# Half-Bridge.net
KiCad netlist of a schematic drawn in Altium Designer
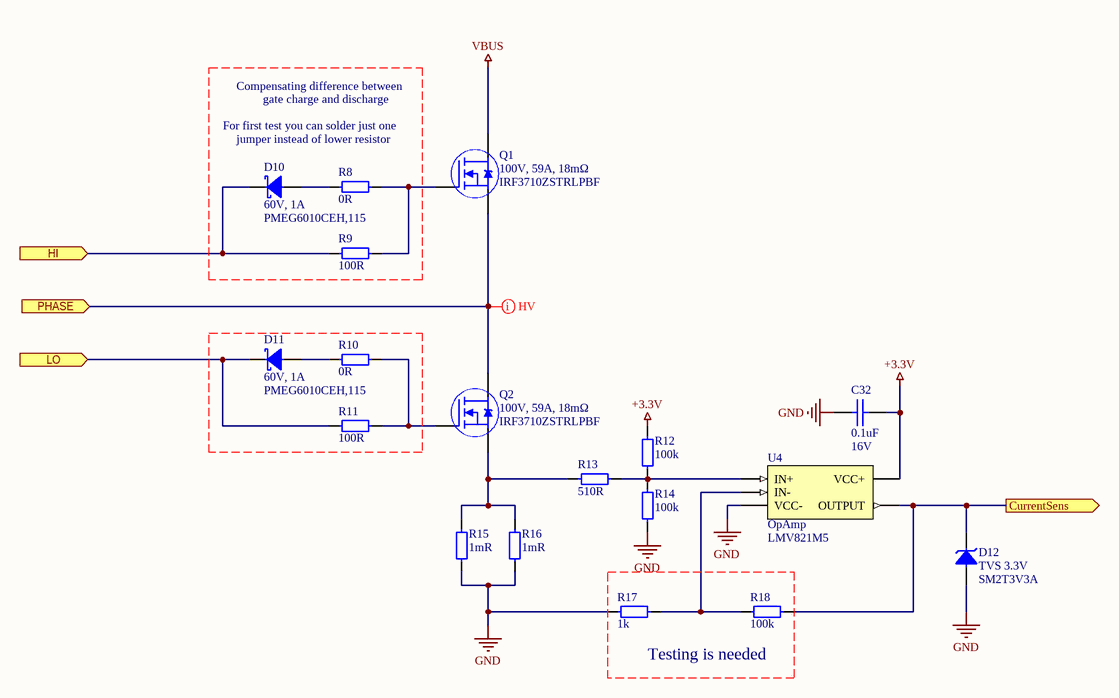
[diagram p0: Half-Bridge.SchDoc]

(export (version "E")
  (design (tool "Eeschema 10.0.6"))
  (components
    (comp (ref "C32")
      (value "0.1uF")
      (footprint "0603 Capicator")
      (description "0.1uF X7R 16V 10% 0603")
      (fields
        (field (name "MANUFACTURER") "Murata Manufacturing")
        (field (name "PART NUMBER") "GRM188R71C104KA01D")
        (field (name "VOLTAGE") "16V")
      )
      (libsource (lib "Karen_Components") (part "Cap 0.1uF (0603)"))
    )
    (comp (ref "D10")
      (value "60V, 1A")
      (footprint "SOD-123FL")
      (fields (field (name "MANUFACTURER") "Nexperia") (field (name "PART NUMBER") "PMEG6010CEH,115"))
      (libsource (lib "Karen_Components") (part "Diode Schottky 60V (SOD-123FL)"))
    )
    (comp (ref "D11")
      (value "60V, 1A")
      (footprint "SOD-123FL")
      (fields (field (name "MANUFACTURER") "Nexperia") (field (name "PART NUMBER") "PMEG6010CEH,115"))
      (libsource (lib "Karen_Components") (part "Diode Schottky 60V (SOD-123FL)"))
    )
    (comp (ref "D12")
      (value "TVS 3.3V")
      (footprint "DO-216AA")
      (description "High peak pulse power: 200 W (10/1000 μs)")
      (fields (field (name "MANUFACTURER") "STMicroelectronics") (field (name "PART NUMBER") "SM2T3V3A"))
      (libsource (lib "Karen_Components") (part "TVS Diode 3.3V [SM2T]"))
    )
    (comp (ref "Q1")
      (value "100V, 59A, 18mΩ")
      (footprint "D2-PAK (TO-262)")
      (fields (field (name "MANUFACTURER") "Infineon") (field (name "PART NUMBER") "IRF3710ZSTRLPBF"))
      (libsource (lib "Karen_Components") (part "MOSFET-N [IRF]"))
    )
    (comp (ref "Q2")
      (value "100V, 59A, 18mΩ")
      (footprint "D2-PAK (TO-262)")
      (fields (field (name "MANUFACTURER") "Infineon") (field (name "PART NUMBER") "IRF3710ZSTRLPBF"))
      (libsource (lib "Karen_Components") (part "MOSFET-N [IRF]"))
    )
    (comp (ref "R8")
      (value "0R")
      (footprint "0603 Resistor")
      (description "0.1W 0603 0R, 5%")
      (fields (field (name "PART NUMBER") "RC0603JR-070RL") (field (name "MANUFACTURER") "Taiwan"))
      (libsource (lib "Karen_Components") (part "Res 0R (0603)"))
    )
    (comp (ref "R9")
      (value "100R")
      (footprint "0603 Resistor")
      (description "0.1W 0603 100R, 1%")
      (fields (field (name "PART NUMBER") "RC0603FR-07100RL") (field (name "MANUFACTURER") "Taiwan"))
      (libsource (lib "Karen_Components") (part "Res 100R (0603)"))
    )
    (comp (ref "R10")
      (value "0R")
      (footprint "0603 Resistor")
      (description "0.1W 0603 0R, 5%")
      (fields (field (name "PART NUMBER") "RC0603JR-070RL") (field (name "MANUFACTURER") "Taiwan"))
      (libsource (lib "Karen_Components") (part "Res 0R (0603)"))
    )
    (comp (ref "R11")
      (value "100R")
      (footprint "0603 Resistor")
      (description "0.1W 0603 100R, 1%")
      (fields (field (name "PART NUMBER") "RC0603FR-07100RL") (field (name "MANUFACTURER") "Taiwan"))
      (libsource (lib "Karen_Components") (part "Res 100R (0603)"))
    )
    (comp (ref "R12")
      (value "100k")
      (footprint "0603 Resistor")
      (description "0.1W 0603 100k, 1%")
      (fields (field (name "PART NUMBER") "RC0603FR-07100KL") (field (name "MANUFACTURER") "Taiwan"))
      (libsource (lib "Karen_Components") (part "Res 100k (0603)"))
    )
    (comp (ref "R13")
      (value "510R")
      (footprint "0603 Resistor")
      (description "0.1W 0603 510R, 1%")
      (fields (field (name "PART NUMBER") "RC0603FR-07510RL") (field (name "MANUFACTURER") "Taiwan"))
      (libsource (lib "Karen_Components") (part "Res 510R (0603)"))
    )
    (comp (ref "R14")
      (value "100k")
      (footprint "0603 Resistor")
      (description "0.1W 0603 100k, 1%")
      (fields (field (name "PART NUMBER") "RC0603FR-07100KL") (field (name "MANUFACTURER") "Taiwan"))
      (libsource (lib "Karen_Components") (part "Res 100k (0603)"))
    )
    (comp (ref "R15")
      (value "1mR")
      (footprint "2512 Resistor")
      (description "Current Shunt, 1W 2512 1mR 1%")
      (fields (field (name "PART NUMBER") "WSL25121L000FEA") (field (name "MANUFACTURER") "Vishay"))
      (libsource (lib "Karen_Components") (part "Res Precise 1mR (2512)"))
    )
    (comp (ref "R16")
      (value "1mR")
      (footprint "2512 Resistor")
      (description "Current Shunt, 1W 2512 1mR 1%")
      (fields (field (name "PART NUMBER") "WSL25121L000FEA") (field (name "MANUFACTURER") "Vishay"))
      (libsource (lib "Karen_Components") (part "Res Precise 1mR (2512)"))
    )
    (comp (ref "R17")
      (value "1k")
      (footprint "0603 Resistor")
      (description "0.1W 0603 1k, 1%")
      (fields (field (name "PART NUMBER") "RC0603FR-071KL") (field (name "MANUFACTURER") "Taiwan"))
      (libsource (lib "Karen_Components") (part "Res 1k (0603)"))
    )
    (comp (ref "R18")
      (value "100k")
      (footprint "0603 Resistor")
      (description "0.1W 0603 100k, 1%")
      (fields (field (name "PART NUMBER") "RC0603FR-07100KL") (field (name "MANUFACTURER") "Taiwan"))
      (libsource (lib "Karen_Components") (part "Res 100k (0603)"))
    )
    (comp (ref "U4")
      (value "OpAmp")
      (footprint "SOT-23-5")
      (fields (field (name "MANUFACTURER") "Texas Instruments") (field (name "PART NUMBER") "LMV821M5"))
      (libsource (lib "Karen_Components") (part "OpAmp [LMV821]"))
    )
  )
  (nets
    (net (code "1") (name "+3.3V") (class "Default")
      (node (ref "C32") (pin "1") (pinfunction "1_1") (pintype "passive"))
      (node (ref "R12") (pin "2") (pinfunction "2_2") (pintype "passive"))
      (node (ref "U4") (pin "5") (pinfunction "VCC+_5") (pintype "power_in"))
    )
    (net (code "2") (name "/CurrentSens") (class "Default")
      (node (ref "D12") (pin "2") (pinfunction "2_2") (pintype "passive"))
      (node (ref "R18") (pin "2") (pinfunction "2_2") (pintype "passive"))
      (node (ref "U4") (pin "4") (pinfunction "OUTPUT_4") (pintype "output"))
    )
    (net (code "3") (name "/HI") (class "Default")
      (node (ref "D10") (pin "2") (pinfunction "2_2") (pintype "passive"))
      (node (ref "R9") (pin "1") (pinfunction "1_1") (pintype "passive"))
    )
    (net (code "4") (name "/LO") (class "Default")
      (node (ref "D11") (pin "2") (pinfunction "2_2") (pintype "passive"))
      (node (ref "R11") (pin "1") (pinfunction "1_1") (pintype "passive"))
    )
    (net (code "5") (name "/PHASE") (class "Default")
      (node (ref "Q1") (pin "3") (pinfunction "Source_3") (pintype "passive"))
      (node (ref "Q2") (pin "2") (pinfunction "Drain_2") (pintype "passive"))
    )
    (net (code "6") (name "GND") (class "Default")
      (node (ref "C32") (pin "2") (pinfunction "2_2") (pintype "passive"))
      (node (ref "D12") (pin "1") (pinfunction "1_1") (pintype "passive"))
      (node (ref "R14") (pin "1") (pinfunction "1_1") (pintype "passive"))
      (node (ref "R15") (pin "1") (pinfunction "1_1") (pintype "passive"))
      (node (ref "R16") (pin "1") (pinfunction "1_1") (pintype "passive"))
      (node (ref "R17") (pin "1") (pinfunction "1_1") (pintype "passive"))
      (node (ref "U4") (pin "2") (pinfunction "VCC-_2") (pintype "power_in"))
    )
    (net (code "7") (name "Net-(D10-Pad1)") (class "Default")
      (node (ref "D10") (pin "1") (pinfunction "1_1") (pintype "passive"))
      (node (ref "R8") (pin "1") (pinfunction "1_1") (pintype "passive"))
    )
    (net (code "8") (name "Net-(D11-Pad1)") (class "Default")
      (node (ref "D11") (pin "1") (pinfunction "1_1") (pintype "passive"))
      (node (ref "R10") (pin "1") (pinfunction "1_1") (pintype "passive"))
    )
    (net (code "9") (name "Net-(Q1-Gate)") (class "Default")
      (node (ref "Q1") (pin "1") (pinfunction "Gate_1") (pintype "passive"))
      (node (ref "R8") (pin "2") (pinfunction "2_2") (pintype "passive"))
      (node (ref "R9") (pin "2") (pinfunction "2_2") (pintype "passive"))
    )
    (net (code "10") (name "Net-(Q2-Gate)") (class "Default")
      (node (ref "Q2") (pin "1") (pinfunction "Gate_1") (pintype "passive"))
      (node (ref "R10") (pin "2") (pinfunction "2_2") (pintype "passive"))
      (node (ref "R11") (pin "2") (pinfunction "2_2") (pintype "passive"))
    )
    (net (code "11") (name "Net-(Q2-Source)") (class "Default")
      (node (ref "Q2") (pin "3") (pinfunction "Source_3") (pintype "passive"))
      (node (ref "R13") (pin "1") (pinfunction "1_1") (pintype "passive"))
      (node (ref "R15") (pin "2") (pinfunction "2_2") (pintype "passive"))
      (node (ref "R16") (pin "2") (pinfunction "2_2") (pintype "passive"))
    )
    (net (code "12") (name "Net-(U4-IN+)") (class "Default")
      (node (ref "R12") (pin "1") (pinfunction "1_1") (pintype "passive"))
      (node (ref "R13") (pin "2") (pinfunction "2_2") (pintype "passive"))
      (node (ref "R14") (pin "2") (pinfunction "2_2") (pintype "passive"))
      (node (ref "U4") (pin "1") (pinfunction "IN+_1") (pintype "input"))
    )
    (net (code "13") (name "Net-(U4-IN-)") (class "Default")
      (node (ref "R17") (pin "2") (pinfunction "2_2") (pintype "passive"))
      (node (ref "R18") (pin "1") (pinfunction "1_1") (pintype "passive"))
      (node (ref "U4") (pin "3") (pinfunction "IN-_3") (pintype "input"))
    )
    (net (code "14") (name "VBUS") (class "Default")
      (node (ref "Q1") (pin "2") (pinfunction "Drain_2") (pintype "passive"))
    )
  )
)
